# modularArduinoClouds3.net
KiCad netlist of a schematic drawn in EAGLE
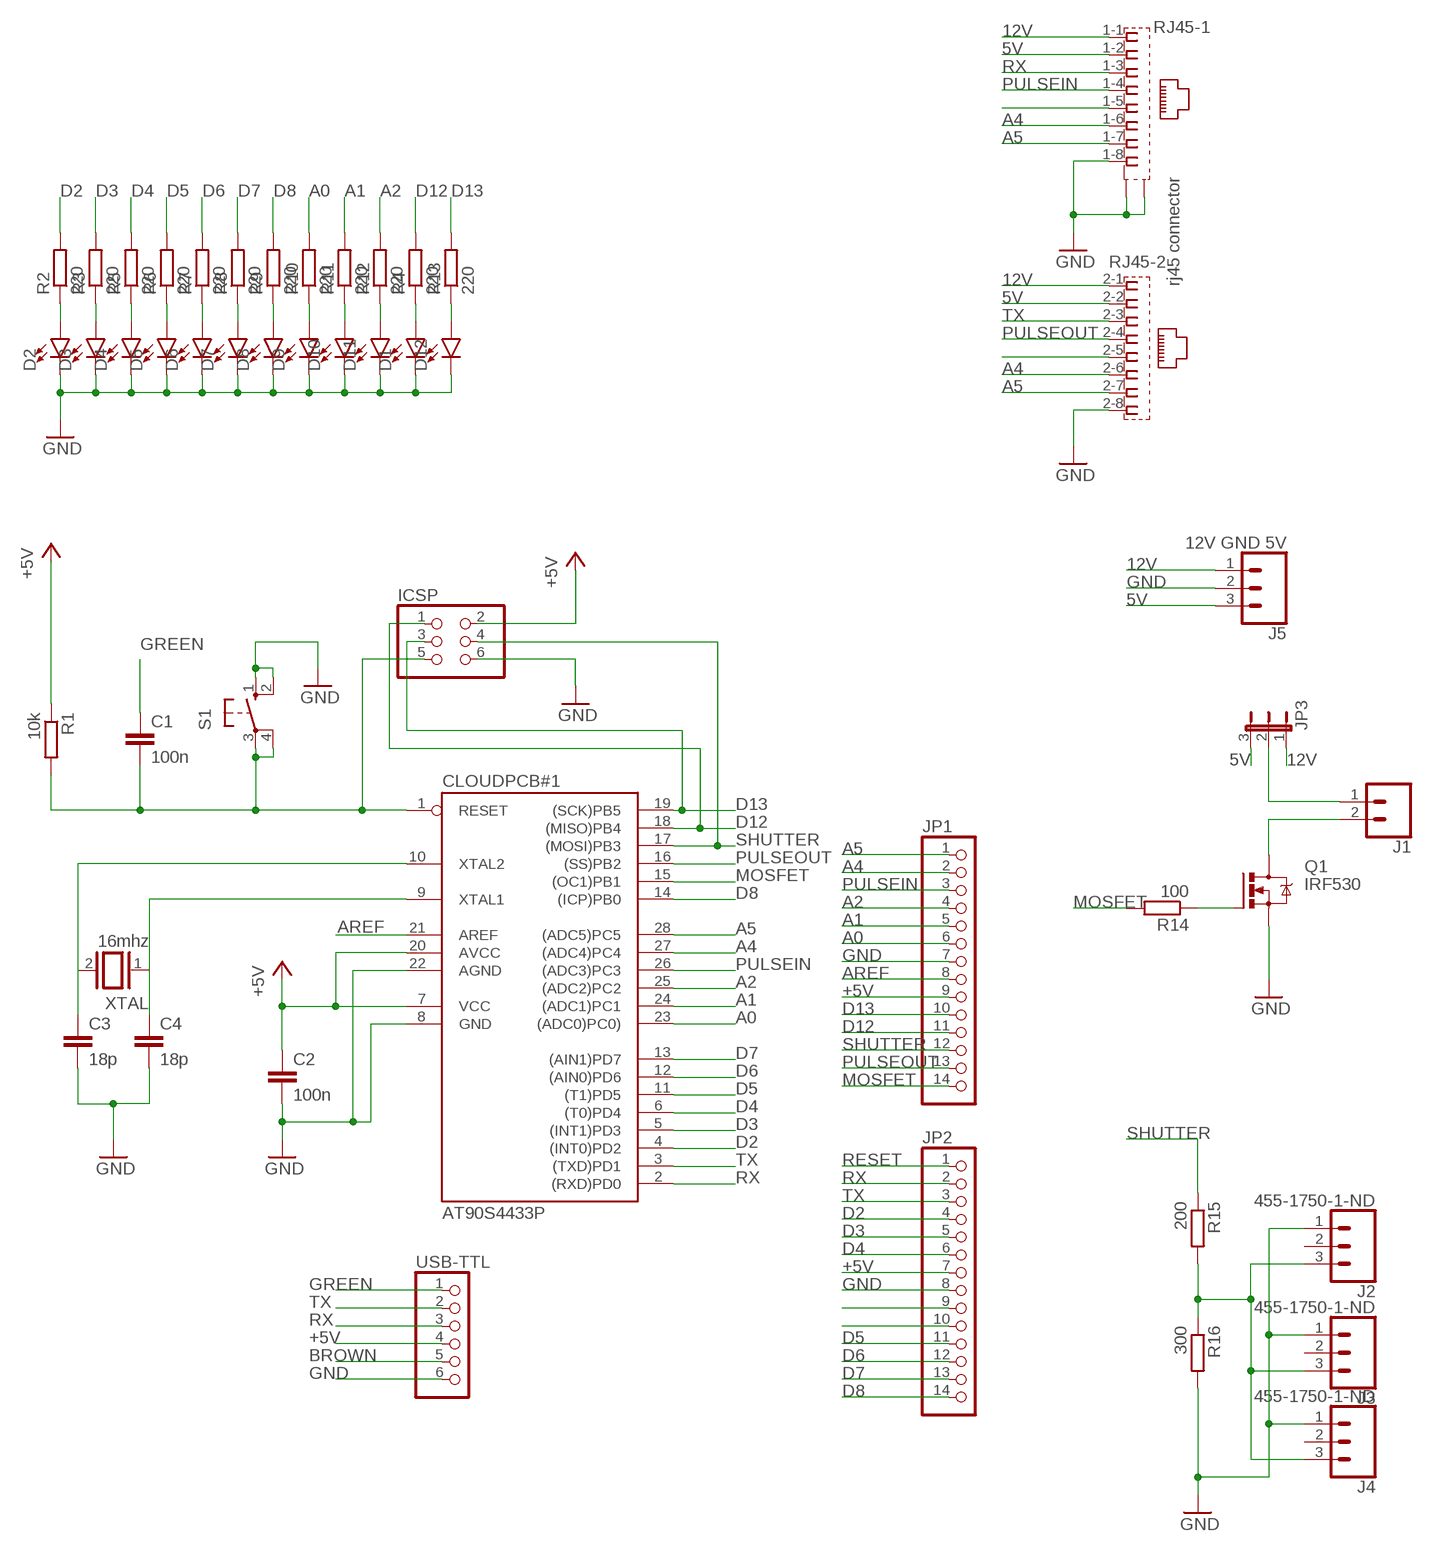
[diagram p0: schematic, sheet 1]

(export (version "E")
  (design (tool "Eeschema 10.0.6"))
  (components
    (comp (ref "C1")
      (value "100n")
      (footprint "eagle-import:C050-025X075")
      (libsource (lib "eagle-import") (part "C-EU050-025X075"))
    )
    (comp (ref "C2")
      (value "100n")
      (footprint "eagle-import:C050-025X075")
      (libsource (lib "eagle-import") (part "C-EU050-025X075"))
    )
    (comp (ref "C3")
      (value "18p")
      (footprint "eagle-import:C050-025X075")
      (libsource (lib "eagle-import") (part "C-EU050-025X075"))
    )
    (comp (ref "C4")
      (value "18p")
      (footprint "eagle-import:C050-025X075")
      (libsource (lib "eagle-import") (part "C-EU050-025X075"))
    )
    (comp (ref "CLOUDPCB#1")
      (value "AT90S4433P")
      (footprint "eagle-import:DIL28-3")
      (libsource (lib "eagle-import") (part "AT90S4433P"))
    )
    (comp (ref "D1")
      (value "LED5MM")
      (footprint "eagle-import:LED_5MM")
      (fields (field (name "SPICEPREFIX") "D"))
      (libsource (lib "eagle-import") (part "LED5MM"))
    )
    (comp (ref "D2")
      (value "LED5MM")
      (footprint "eagle-import:LED_5MM")
      (fields (field (name "SPICEPREFIX") "D"))
      (libsource (lib "eagle-import") (part "LED5MM"))
    )
    (comp (ref "D3")
      (value "LED5MM")
      (footprint "eagle-import:LED_5MM")
      (fields (field (name "SPICEPREFIX") "D"))
      (libsource (lib "eagle-import") (part "LED5MM"))
    )
    (comp (ref "D4")
      (value "LED5MM")
      (footprint "eagle-import:LED_5MM")
      (fields (field (name "SPICEPREFIX") "D"))
      (libsource (lib "eagle-import") (part "LED5MM"))
    )
    (comp (ref "D5")
      (value "LED5MM")
      (footprint "eagle-import:LED_5MM")
      (fields (field (name "SPICEPREFIX") "D"))
      (libsource (lib "eagle-import") (part "LED5MM"))
    )
    (comp (ref "D6")
      (value "LED5MM")
      (footprint "eagle-import:LED_5MM")
      (fields (field (name "SPICEPREFIX") "D"))
      (libsource (lib "eagle-import") (part "LED5MM"))
    )
    (comp (ref "D7")
      (value "LED5MM")
      (footprint "eagle-import:LED_5MM")
      (fields (field (name "SPICEPREFIX") "D"))
      (libsource (lib "eagle-import") (part "LED5MM"))
    )
    (comp (ref "D8")
      (value "LED5MM")
      (footprint "eagle-import:LED_5MM")
      (fields (field (name "SPICEPREFIX") "D"))
      (libsource (lib "eagle-import") (part "LED5MM"))
    )
    (comp (ref "D9")
      (value "LED5MM")
      (footprint "eagle-import:LED_5MM")
      (fields (field (name "SPICEPREFIX") "D"))
      (libsource (lib "eagle-import") (part "LED5MM"))
    )
    (comp (ref "D10")
      (value "LED5MM")
      (footprint "eagle-import:LED_5MM")
      (fields (field (name "SPICEPREFIX") "D"))
      (libsource (lib "eagle-import") (part "LED5MM"))
    )
    (comp (ref "D11")
      (value "LED5MM")
      (footprint "eagle-import:LED_5MM")
      (fields (field (name "SPICEPREFIX") "D"))
      (libsource (lib "eagle-import") (part "LED5MM"))
    )
    (comp (ref "D12")
      (value "LED5MM")
      (footprint "eagle-import:LED_5MM")
      (fields (field (name "SPICEPREFIX") "D"))
      (libsource (lib "eagle-import") (part "LED5MM"))
    )
    (comp (ref "ICSP")
      (value "PINHD-2X3")
      (footprint "eagle-import:2X03")
      (libsource (lib "eagle-import") (part "PINHD-2X3"))
    )
    (comp (ref "J1")
      (value "CONN_02")
      (footprint "eagle-import:1X02")
      (libsource (lib "eagle-import") (part "CONN_02"))
    )
    (comp (ref "J2")
      (value "455-1750-1-ND")
      (footprint "eagle-import:1X03")
      (libsource (lib "eagle-import") (part "CONN_03"))
    )
    (comp (ref "J3")
      (value "455-1750-1-ND")
      (footprint "eagle-import:1X03")
      (libsource (lib "eagle-import") (part "CONN_03"))
    )
    (comp (ref "J4")
      (value "455-1750-1-ND")
      (footprint "eagle-import:1X03")
      (libsource (lib "eagle-import") (part "CONN_03"))
    )
    (comp (ref "J5")
      (value "12V GND 5V")
      (footprint "eagle-import:1X03")
      (libsource (lib "eagle-import") (part "CONN_03"))
    )
    (comp (ref "JP1")
      (value "PINHD-1X14")
      (footprint "eagle-import:1X14")
      (libsource (lib "eagle-import") (part "PINHD-1X14"))
    )
    (comp (ref "JP2")
      (value "PINHD-1X14")
      (footprint "eagle-import:1X14")
      (libsource (lib "eagle-import") (part "PINHD-1X14"))
    )
    (comp (ref "JP3")
      (value "JP2E")
      (footprint "eagle-import:JP2")
      (libsource (lib "eagle-import") (part "JP2E"))
    )
    (comp (ref "Q1")
      (value "IRF530")
      (footprint "eagle-import:TO220BV")
      (libsource (lib "eagle-import") (part "IRF530"))
    )
    (comp (ref "R1")
      (value "10k")
      (footprint "eagle-import:0207_10")
      (libsource (lib "eagle-import") (part "R-EU_0207/10"))
    )
    (comp (ref "R2")
      (value "220")
      (footprint "eagle-import:0207_10")
      (libsource (lib "eagle-import") (part "R-EU_0207/10"))
    )
    (comp (ref "R3")
      (value "220")
      (footprint "eagle-import:0207_10")
      (libsource (lib "eagle-import") (part "R-EU_0207/10"))
    )
    (comp (ref "R4")
      (value "220")
      (footprint "eagle-import:0207_10")
      (libsource (lib "eagle-import") (part "R-EU_0207/10"))
    )
    (comp (ref "R5")
      (value "220")
      (footprint "eagle-import:0207_10")
      (libsource (lib "eagle-import") (part "R-EU_0207/10"))
    )
    (comp (ref "R6")
      (value "220")
      (footprint "eagle-import:0207_10")
      (libsource (lib "eagle-import") (part "R-EU_0207/10"))
    )
    (comp (ref "R7")
      (value "220")
      (footprint "eagle-import:0207_10")
      (libsource (lib "eagle-import") (part "R-EU_0207/10"))
    )
    (comp (ref "R8")
      (value "220")
      (footprint "eagle-import:0207_10")
      (libsource (lib "eagle-import") (part "R-EU_0207/10"))
    )
    (comp (ref "R9")
      (value "220")
      (footprint "eagle-import:0207_10")
      (libsource (lib "eagle-import") (part "R-EU_0207/10"))
    )
    (comp (ref "R10")
      (value "220")
      (footprint "eagle-import:0207_10")
      (libsource (lib "eagle-import") (part "R-EU_0207/10"))
    )
    (comp (ref "R11")
      (value "220")
      (footprint "eagle-import:0207_10")
      (libsource (lib "eagle-import") (part "R-EU_0207/10"))
    )
    (comp (ref "R12")
      (value "220")
      (footprint "eagle-import:0207_10")
      (libsource (lib "eagle-import") (part "R-EU_0207/10"))
    )
    (comp (ref "R13")
      (value "220")
      (footprint "eagle-import:0207_10")
      (libsource (lib "eagle-import") (part "R-EU_0207/10"))
    )
    (comp (ref "R14")
      (value "100")
      (footprint "eagle-import:0207_10")
      (libsource (lib "eagle-import") (part "R-EU_0207/10"))
    )
    (comp (ref "R15")
      (value "200")
      (footprint "eagle-import:0207_10")
      (libsource (lib "eagle-import") (part "R-EU_0207/10"))
    )
    (comp (ref "R16")
      (value "300")
      (footprint "eagle-import:0207_10")
      (libsource (lib "eagle-import") (part "R-EU_0207/10"))
    )
    (comp (ref "RJ45")
      (value "557570-1")
      (footprint "eagle-import:557570-1")
      (libsource (lib "eagle-import") (part "557570-1"))
    )
    (comp (ref "S1")
      (value "10-XX")
      (footprint "eagle-import:B3F-10XX")
      (fields (field (name "MPN") "B3F-1000"))
      (libsource (lib "eagle-import") (part "10-XX"))
    )
    (comp (ref "USB-TTL")
      (value "PINHD-1X6")
      (footprint "eagle-import:1X06")
      (libsource (lib "eagle-import") (part "PINHD-1X6"))
    )
    (comp (ref "XTAL")
      (value "16mhz")
      (footprint "eagle-import:QS")
      (libsource (lib "eagle-import") (part "XTAL/S"))
    )
  )
  (nets
    (net (code "1") (name "+5V") (class "Default")
      (node (ref "C2") (pin "1") (pinfunction "1_1") (pintype "passive"))
      (node (ref "CLOUDPCB#1") (pin "20") (pinfunction "AVCC_20") (pintype "power_in"))
      (node (ref "CLOUDPCB#1") (pin "7") (pinfunction "VCC_7") (pintype "power_in"))
      (node (ref "ICSP") (pin "2") (pinfunction "2_2") (pintype "passive"))
      (node (ref "JP1") (pin "9") (pinfunction "9_9") (pintype "passive"))
      (node (ref "JP2") (pin "7") (pinfunction "7_7") (pintype "passive"))
      (node (ref "R1") (pin "1") (pinfunction "1_1") (pintype "passive"))
      (node (ref "USB-TTL") (pin "4") (pinfunction "4_4") (pintype "passive"))
    )
    (net (code "2") (name "/5V") (class "Default")
      (node (ref "J5") (pin "3") (pinfunction "3_3") (pintype "passive"))
      (node (ref "JP3") (pin "3") (pinfunction "3_3") (pintype "passive"))
      (node (ref "RJ45") (pin "1-2") (pinfunction "2_1-2") (pintype "passive"))
      (node (ref "RJ45") (pin "2-2") (pinfunction "2_2-2") (pintype "passive"))
    )
    (net (code "3") (name "/12V") (class "Default")
      (node (ref "J5") (pin "1") (pinfunction "1_1") (pintype "passive"))
      (node (ref "JP3") (pin "1") (pinfunction "1_1") (pintype "passive"))
      (node (ref "RJ45") (pin "1-1") (pinfunction "1_1-1") (pintype "passive"))
      (node (ref "RJ45") (pin "2-1") (pinfunction "1_2-1") (pintype "passive"))
    )
    (net (code "4") (name "/A0") (class "Default")
      (node (ref "CLOUDPCB#1") (pin "23") (pinfunction "(ADC0)PC0)_23") (pintype "bidirectional"))
      (node (ref "JP1") (pin "6") (pinfunction "6_6") (pintype "passive"))
      (node (ref "R10") (pin "2") (pinfunction "2_2") (pintype "passive"))
    )
    (net (code "5") (name "/A1") (class "Default")
      (node (ref "CLOUDPCB#1") (pin "24") (pinfunction "(ADC1)PC1_24") (pintype "bidirectional"))
      (node (ref "JP1") (pin "5") (pinfunction "5_5") (pintype "passive"))
      (node (ref "R11") (pin "2") (pinfunction "2_2") (pintype "passive"))
    )
    (net (code "6") (name "/A2") (class "Default")
      (node (ref "CLOUDPCB#1") (pin "25") (pinfunction "(ADC2)PC2_25") (pintype "bidirectional"))
      (node (ref "JP1") (pin "4") (pinfunction "4_4") (pintype "passive"))
      (node (ref "R12") (pin "2") (pinfunction "2_2") (pintype "passive"))
    )
    (net (code "7") (name "/A4") (class "Default")
      (node (ref "CLOUDPCB#1") (pin "27") (pinfunction "(ADC4)PC4_27") (pintype "bidirectional"))
      (node (ref "JP1") (pin "2") (pinfunction "2_2") (pintype "passive"))
      (node (ref "RJ45") (pin "1-6") (pinfunction "6_1-6") (pintype "passive"))
      (node (ref "RJ45") (pin "2-6") (pinfunction "6_2-6") (pintype "passive"))
    )
    (net (code "8") (name "/A5") (class "Default")
      (node (ref "CLOUDPCB#1") (pin "28") (pinfunction "(ADC5)PC5_28") (pintype "bidirectional"))
      (node (ref "JP1") (pin "1") (pinfunction "1_1") (pintype "passive"))
      (node (ref "RJ45") (pin "1-7") (pinfunction "7_1-7") (pintype "passive"))
      (node (ref "RJ45") (pin "2-7") (pinfunction "7_2-7") (pintype "passive"))
    )
    (net (code "9") (name "/AREF") (class "Default")
      (node (ref "CLOUDPCB#1") (pin "21") (pinfunction "AREF_21") (pintype "passive"))
      (node (ref "JP1") (pin "8") (pinfunction "8_8") (pintype "passive"))
    )
    (net (code "10") (name "/BROWN") (class "Default")
      (node (ref "USB-TTL") (pin "5") (pinfunction "5_5") (pintype "passive"))
    )
    (net (code "11") (name "/D2") (class "Default")
      (node (ref "CLOUDPCB#1") (pin "4") (pinfunction "(INT0)PD2_4") (pintype "bidirectional"))
      (node (ref "JP2") (pin "4") (pinfunction "4_4") (pintype "passive"))
      (node (ref "R2") (pin "2") (pinfunction "2_2") (pintype "passive"))
    )
    (net (code "12") (name "/D3") (class "Default")
      (node (ref "CLOUDPCB#1") (pin "5") (pinfunction "(INT1)PD3_5") (pintype "bidirectional"))
      (node (ref "JP2") (pin "5") (pinfunction "5_5") (pintype "passive"))
      (node (ref "R3") (pin "2") (pinfunction "2_2") (pintype "passive"))
    )
    (net (code "13") (name "/D4") (class "Default")
      (node (ref "CLOUDPCB#1") (pin "6") (pinfunction "(T0)PD4_6") (pintype "bidirectional"))
      (node (ref "JP2") (pin "6") (pinfunction "6_6") (pintype "passive"))
      (node (ref "R5") (pin "2") (pinfunction "2_2") (pintype "passive"))
    )
    (net (code "14") (name "/D5") (class "Default")
      (node (ref "CLOUDPCB#1") (pin "11") (pinfunction "(T1)PD5_11") (pintype "bidirectional"))
      (node (ref "JP2") (pin "11") (pinfunction "11_11") (pintype "passive"))
      (node (ref "R6") (pin "2") (pinfunction "2_2") (pintype "passive"))
    )
    (net (code "15") (name "/D6") (class "Default")
      (node (ref "CLOUDPCB#1") (pin "12") (pinfunction "(AIN0)PD6_12") (pintype "bidirectional"))
      (node (ref "JP2") (pin "12") (pinfunction "12_12") (pintype "passive"))
      (node (ref "R7") (pin "2") (pinfunction "2_2") (pintype "passive"))
    )
    (net (code "16") (name "/D7") (class "Default")
      (node (ref "CLOUDPCB#1") (pin "13") (pinfunction "(AIN1)PD7_13") (pintype "bidirectional"))
      (node (ref "JP2") (pin "13") (pinfunction "13_13") (pintype "passive"))
      (node (ref "R8") (pin "2") (pinfunction "2_2") (pintype "passive"))
    )
    (net (code "17") (name "/D8") (class "Default")
      (node (ref "CLOUDPCB#1") (pin "14") (pinfunction "(ICP)PB0_14") (pintype "bidirectional"))
      (node (ref "JP2") (pin "14") (pinfunction "14_14") (pintype "passive"))
      (node (ref "R9") (pin "2") (pinfunction "2_2") (pintype "passive"))
    )
    (net (code "18") (name "/D12") (class "Default")
      (node (ref "CLOUDPCB#1") (pin "18") (pinfunction "(MISO)PB4_18") (pintype "bidirectional"))
      (node (ref "ICSP") (pin "1") (pinfunction "1_1") (pintype "passive"))
      (node (ref "JP1") (pin "11") (pinfunction "11_11") (pintype "passive"))
      (node (ref "R4") (pin "2") (pinfunction "2_2") (pintype "passive"))
    )
    (net (code "19") (name "/D13") (class "Default")
      (node (ref "CLOUDPCB#1") (pin "19") (pinfunction "(SCK)PB5_19") (pintype "bidirectional"))
      (node (ref "ICSP") (pin "3") (pinfunction "3_3") (pintype "passive"))
      (node (ref "JP1") (pin "10") (pinfunction "10_10") (pintype "passive"))
      (node (ref "R13") (pin "2") (pinfunction "2_2") (pintype "passive"))
    )
    (net (code "20") (name "/GREEN") (class "Default")
      (node (ref "C1") (pin "1") (pinfunction "1_1") (pintype "passive"))
      (node (ref "USB-TTL") (pin "1") (pinfunction "1_1") (pintype "passive"))
    )
    (net (code "21") (name "/MOSFET") (class "Default")
      (node (ref "CLOUDPCB#1") (pin "15") (pinfunction "(OC1)PB1_15") (pintype "bidirectional"))
      (node (ref "JP1") (pin "14") (pinfunction "14_14") (pintype "passive"))
      (node (ref "R14") (pin "2") (pinfunction "2_2") (pintype "passive"))
    )
    (net (code "22") (name "/PULSEIN") (class "Default")
      (node (ref "CLOUDPCB#1") (pin "26") (pinfunction "(ADC3)PC3_26") (pintype "bidirectional"))
      (node (ref "JP1") (pin "3") (pinfunction "3_3") (pintype "passive"))
      (node (ref "RJ45") (pin "1-4") (pinfunction "4_1-4") (pintype "passive"))
    )
    (net (code "23") (name "/PULSEOUT") (class "Default")
      (node (ref "CLOUDPCB#1") (pin "16") (pinfunction "(SS)PB2_16") (pintype "bidirectional"))
      (node (ref "JP1") (pin "13") (pinfunction "13_13") (pintype "passive"))
      (node (ref "RJ45") (pin "2-4") (pinfunction "4_2-4") (pintype "passive"))
    )
    (net (code "24") (name "/RESET") (class "Default")
      (node (ref "C1") (pin "2") (pinfunction "2_2") (pintype "passive"))
      (node (ref "CLOUDPCB#1") (pin "1") (pinfunction "RESET_1") (pintype "input"))
      (node (ref "ICSP") (pin "5") (pinfunction "5_5") (pintype "passive"))
      (node (ref "JP2") (pin "1") (pinfunction "1_1") (pintype "passive"))
      (node (ref "R1") (pin "2") (pinfunction "2_2") (pintype "passive"))
      (node (ref "S1") (pin "3") (pinfunction "P_3") (pintype "passive"))
      (node (ref "S1") (pin "4") (pinfunction "P1_4") (pintype "passive"))
    )
    (net (code "25") (name "/RX") (class "Default")
      (node (ref "CLOUDPCB#1") (pin "2") (pinfunction "(RXD)PD0_2") (pintype "bidirectional"))
      (node (ref "JP2") (pin "2") (pinfunction "2_2") (pintype "passive"))
      (node (ref "RJ45") (pin "1-3") (pinfunction "3_1-3") (pintype "passive"))
      (node (ref "USB-TTL") (pin "3") (pinfunction "3_3") (pintype "passive"))
    )
    (net (code "26") (name "/SHUTTER") (class "Default")
      (node (ref "CLOUDPCB#1") (pin "17") (pinfunction "(MOSI)PB3_17") (pintype "bidirectional"))
      (node (ref "ICSP") (pin "4") (pinfunction "4_4") (pintype "passive"))
      (node (ref "JP1") (pin "12") (pinfunction "12_12") (pintype "passive"))
      (node (ref "R15") (pin "1") (pinfunction "1_1") (pintype "passive"))
    )
    (net (code "27") (name "/TX") (class "Default")
      (node (ref "CLOUDPCB#1") (pin "3") (pinfunction "(TXD)PD1_3") (pintype "bidirectional"))
      (node (ref "JP2") (pin "3") (pinfunction "3_3") (pintype "passive"))
      (node (ref "RJ45") (pin "2-3") (pinfunction "3_2-3") (pintype "passive"))
      (node (ref "USB-TTL") (pin "2") (pinfunction "2_2") (pintype "passive"))
    )
    (net (code "28") (name "GND") (class "Default")
      (node (ref "C2") (pin "2") (pinfunction "2_2") (pintype "passive"))
      (node (ref "C3") (pin "2") (pinfunction "2_2") (pintype "passive"))
      (node (ref "C4") (pin "2") (pinfunction "2_2") (pintype "passive"))
      (node (ref "CLOUDPCB#1") (pin "22") (pinfunction "AGND_22") (pintype "power_in"))
      (node (ref "CLOUDPCB#1") (pin "8") (pinfunction "GND_8") (pintype "power_in"))
      (node (ref "D1") (pin "K") (pinfunction "C_K") (pintype "passive"))
      (node (ref "D10") (pin "K") (pinfunction "C_K") (pintype "passive"))
      (node (ref "D11") (pin "K") (pinfunction "C_K") (pintype "passive"))
      (node (ref "D12") (pin "K") (pinfunction "C_K") (pintype "passive"))
      (node (ref "D2") (pin "K") (pinfunction "C_K") (pintype "passive"))
      (node (ref "D3") (pin "K") (pinfunction "C_K") (pintype "passive"))
      (node (ref "D4") (pin "K") (pinfunction "C_K") (pintype "passive"))
      (node (ref "D5") (pin "K") (pinfunction "C_K") (pintype "passive"))
      (node (ref "D6") (pin "K") (pinfunction "C_K") (pintype "passive"))
      (node (ref "D7") (pin "K") (pinfunction "C_K") (pintype "passive"))
      (node (ref "D8") (pin "K") (pinfunction "C_K") (pintype "passive"))
      (node (ref "D9") (pin "K") (pinfunction "C_K") (pintype "passive"))
      (node (ref "ICSP") (pin "6") (pinfunction "6_6") (pintype "passive"))
      (node (ref "J2") (pin "1") (pinfunction "1_1") (pintype "passive"))
      (node (ref "J3") (pin "1") (pinfunction "1_1") (pintype "passive"))
      (node (ref "J4") (pin "1") (pinfunction "1_1") (pintype "passive"))
      (node (ref "J5") (pin "2") (pinfunction "2_2") (pintype "passive"))
      (node (ref "JP1") (pin "7") (pinfunction "7_7") (pintype "passive"))
      (node (ref "JP2") (pin "8") (pinfunction "8_8") (pintype "passive"))
      (node (ref "Q1") (pin "S") (pinfunction "S_S") (pintype "passive"))
      (node (ref "R16") (pin "2") (pinfunction "2_2") (pintype "passive"))
      (node (ref "RJ45") (pin "1-8") (pinfunction "8_1-8") (pintype "passive"))
      (node (ref "RJ45") (pin "2-8") (pinfunction "8_2-8") (pintype "passive"))
      (node (ref "RJ45") (pin "G1") (pinfunction "S2_G1") (pintype "passive"))
      (node (ref "RJ45") (pin "G3") (pinfunction "S1_G3") (pintype "passive"))
      (node (ref "S1") (pin "1") (pinfunction "S_1") (pintype "passive"))
      (node (ref "S1") (pin "2") (pinfunction "S1_2") (pintype "passive"))
      (node (ref "USB-TTL") (pin "6") (pinfunction "6_6") (pintype "passive"))
    )
    (net (code "29") (name "Net-(CLOUDPCB#1-XTAL1)") (class "Default")
      (node (ref "C4") (pin "1") (pinfunction "1_1") (pintype "passive"))
      (node (ref "CLOUDPCB#1") (pin "9") (pinfunction "XTAL1_9") (pintype "bidirectional"))
      (node (ref "XTAL") (pin "1") (pinfunction "1_1") (pintype "passive"))
    )
    (net (code "30") (name "Net-(CLOUDPCB#1-XTAL2)") (class "Default")
      (node (ref "C3") (pin "1") (pinfunction "1_1") (pintype "passive"))
      (node (ref "CLOUDPCB#1") (pin "10") (pinfunction "XTAL2_10") (pintype "bidirectional"))
      (node (ref "XTAL") (pin "2") (pinfunction "2_2") (pintype "passive"))
    )
    (net (code "31") (name "Net-(D1-PadA)") (class "Default")
      (node (ref "D1") (pin "A") (pinfunction "A_A") (pintype "passive"))
      (node (ref "R4") (pin "1") (pinfunction "1_1") (pintype "passive"))
    )
    (net (code "32") (name "Net-(D2-PadA)") (class "Default")
      (node (ref "D2") (pin "A") (pinfunction "A_A") (pintype "passive"))
      (node (ref "R2") (pin "1") (pinfunction "1_1") (pintype "passive"))
    )
    (net (code "33") (name "Net-(D3-PadA)") (class "Default")
      (node (ref "D3") (pin "A") (pinfunction "A_A") (pintype "passive"))
      (node (ref "R3") (pin "1") (pinfunction "1_1") (pintype "passive"))
    )
    (net (code "34") (name "Net-(D4-PadA)") (class "Default")
      (node (ref "D4") (pin "A") (pinfunction "A_A") (pintype "passive"))
      (node (ref "R5") (pin "1") (pinfunction "1_1") (pintype "passive"))
    )
    (net (code "35") (name "Net-(D5-PadA)") (class "Default")
      (node (ref "D5") (pin "A") (pinfunction "A_A") (pintype "passive"))
      (node (ref "R6") (pin "1") (pinfunction "1_1") (pintype "passive"))
    )
    (net (code "36") (name "Net-(D6-PadA)") (class "Default")
      (node (ref "D6") (pin "A") (pinfunction "A_A") (pintype "passive"))
      (node (ref "R7") (pin "1") (pinfunction "1_1") (pintype "passive"))
    )
    (net (code "37") (name "Net-(D7-PadA)") (class "Default")
      (node (ref "D7") (pin "A") (pinfunction "A_A") (pintype "passive"))
      (node (ref "R8") (pin "1") (pinfunction "1_1") (pintype "passive"))
    )
    (net (code "38") (name "Net-(D8-PadA)") (class "Default")
      (node (ref "D8") (pin "A") (pinfunction "A_A") (pintype "passive"))
      (node (ref "R9") (pin "1") (pinfunction "1_1") (pintype "passive"))
    )
    (net (code "39") (name "Net-(D9-PadA)") (class "Default")
      (node (ref "D9") (pin "A") (pinfunction "A_A") (pintype "passive"))
      (node (ref "R10") (pin "1") (pinfunction "1_1") (pintype "passive"))
    )
    (net (code "40") (name "Net-(D10-PadA)") (class "Default")
      (node (ref "D10") (pin "A") (pinfunction "A_A") (pintype "passive"))
      (node (ref "R11") (pin "1") (pinfunction "1_1") (pintype "passive"))
    )
    (net (code "41") (name "Net-(D11-PadA)") (class "Default")
      (node (ref "D11") (pin "A") (pinfunction "A_A") (pintype "passive"))
      (node (ref "R12") (pin "1") (pinfunction "1_1") (pintype "passive"))
    )
    (net (code "42") (name "Net-(D12-PadA)") (class "Default")
      (node (ref "D12") (pin "A") (pinfunction "A_A") (pintype "passive"))
      (node (ref "R13") (pin "1") (pinfunction "1_1") (pintype "passive"))
    )
    (net (code "43") (name "Net-(J1-Pad1)") (class "Default")
      (node (ref "J1") (pin "1") (pinfunction "1_1") (pintype "passive"))
      (node (ref "JP3") (pin "2") (pinfunction "2_2") (pintype "passive"))
    )
    (net (code "44") (name "Net-(J1-Pad2)") (class "Default")
      (node (ref "J1") (pin "2") (pinfunction "2_2") (pintype "passive"))
      (node (ref "Q1") (pin "D") (pinfunction "D_D") (pintype "passive"))
    )
    (net (code "45") (name "Net-(J2-Pad3)") (class "Default")
      (node (ref "J2") (pin "3") (pinfunction "3_3") (pintype "passive"))
      (node (ref "J3") (pin "3") (pinfunction "3_3") (pintype "passive"))
      (node (ref "J4") (pin "3") (pinfunction "3_3") (pintype "passive"))
      (node (ref "R15") (pin "2") (pinfunction "2_2") (pintype "passive"))
      (node (ref "R16") (pin "1") (pinfunction "1_1") (pintype "passive"))
    )
    (net (code "46") (name "Net-(Q1-PadG)") (class "Default")
      (node (ref "Q1") (pin "G") (pinfunction "G_G") (pintype "passive"))
      (node (ref "R14") (pin "1") (pinfunction "1_1") (pintype "passive"))
    )
    (net (code "47") (name "unconnected-(J2-Pad2)") (class "Default")
      (node (ref "J2") (pin "2") (pinfunction "2_2") (pintype "passive"))
    )
    (net (code "48") (name "unconnected-(J3-Pad2)") (class "Default")
      (node (ref "J3") (pin "2") (pinfunction "2_2") (pintype "passive"))
    )
    (net (code "49") (name "unconnected-(J4-Pad2)") (class "Default")
      (node (ref "J4") (pin "2") (pinfunction "2_2") (pintype "passive"))
    )
    (net (code "50") (name "unconnected-(JP2-Pad9)") (class "Default")
      (node (ref "JP2") (pin "9") (pinfunction "9_9") (pintype "passive"))
    )
    (net (code "51") (name "unconnected-(JP2-Pad10)") (class "Default")
      (node (ref "JP2") (pin "10") (pinfunction "10_10") (pintype "passive"))
    )
    (net (code "52") (name "unconnected-(RJ45A-5-Pad1-5)") (class "Default")
      (node (ref "RJ45") (pin "1-5") (pinfunction "5_1-5") (pintype "passive"))
    )
    (net (code "53") (name "unconnected-(RJ45B-5-Pad2-5)") (class "Default")
      (node (ref "RJ45") (pin "2-5") (pinfunction "5_2-5") (pintype "passive"))
    )
  )
)
